# main_board.net
KiCad netlist of a schematic drawn in EAGLE
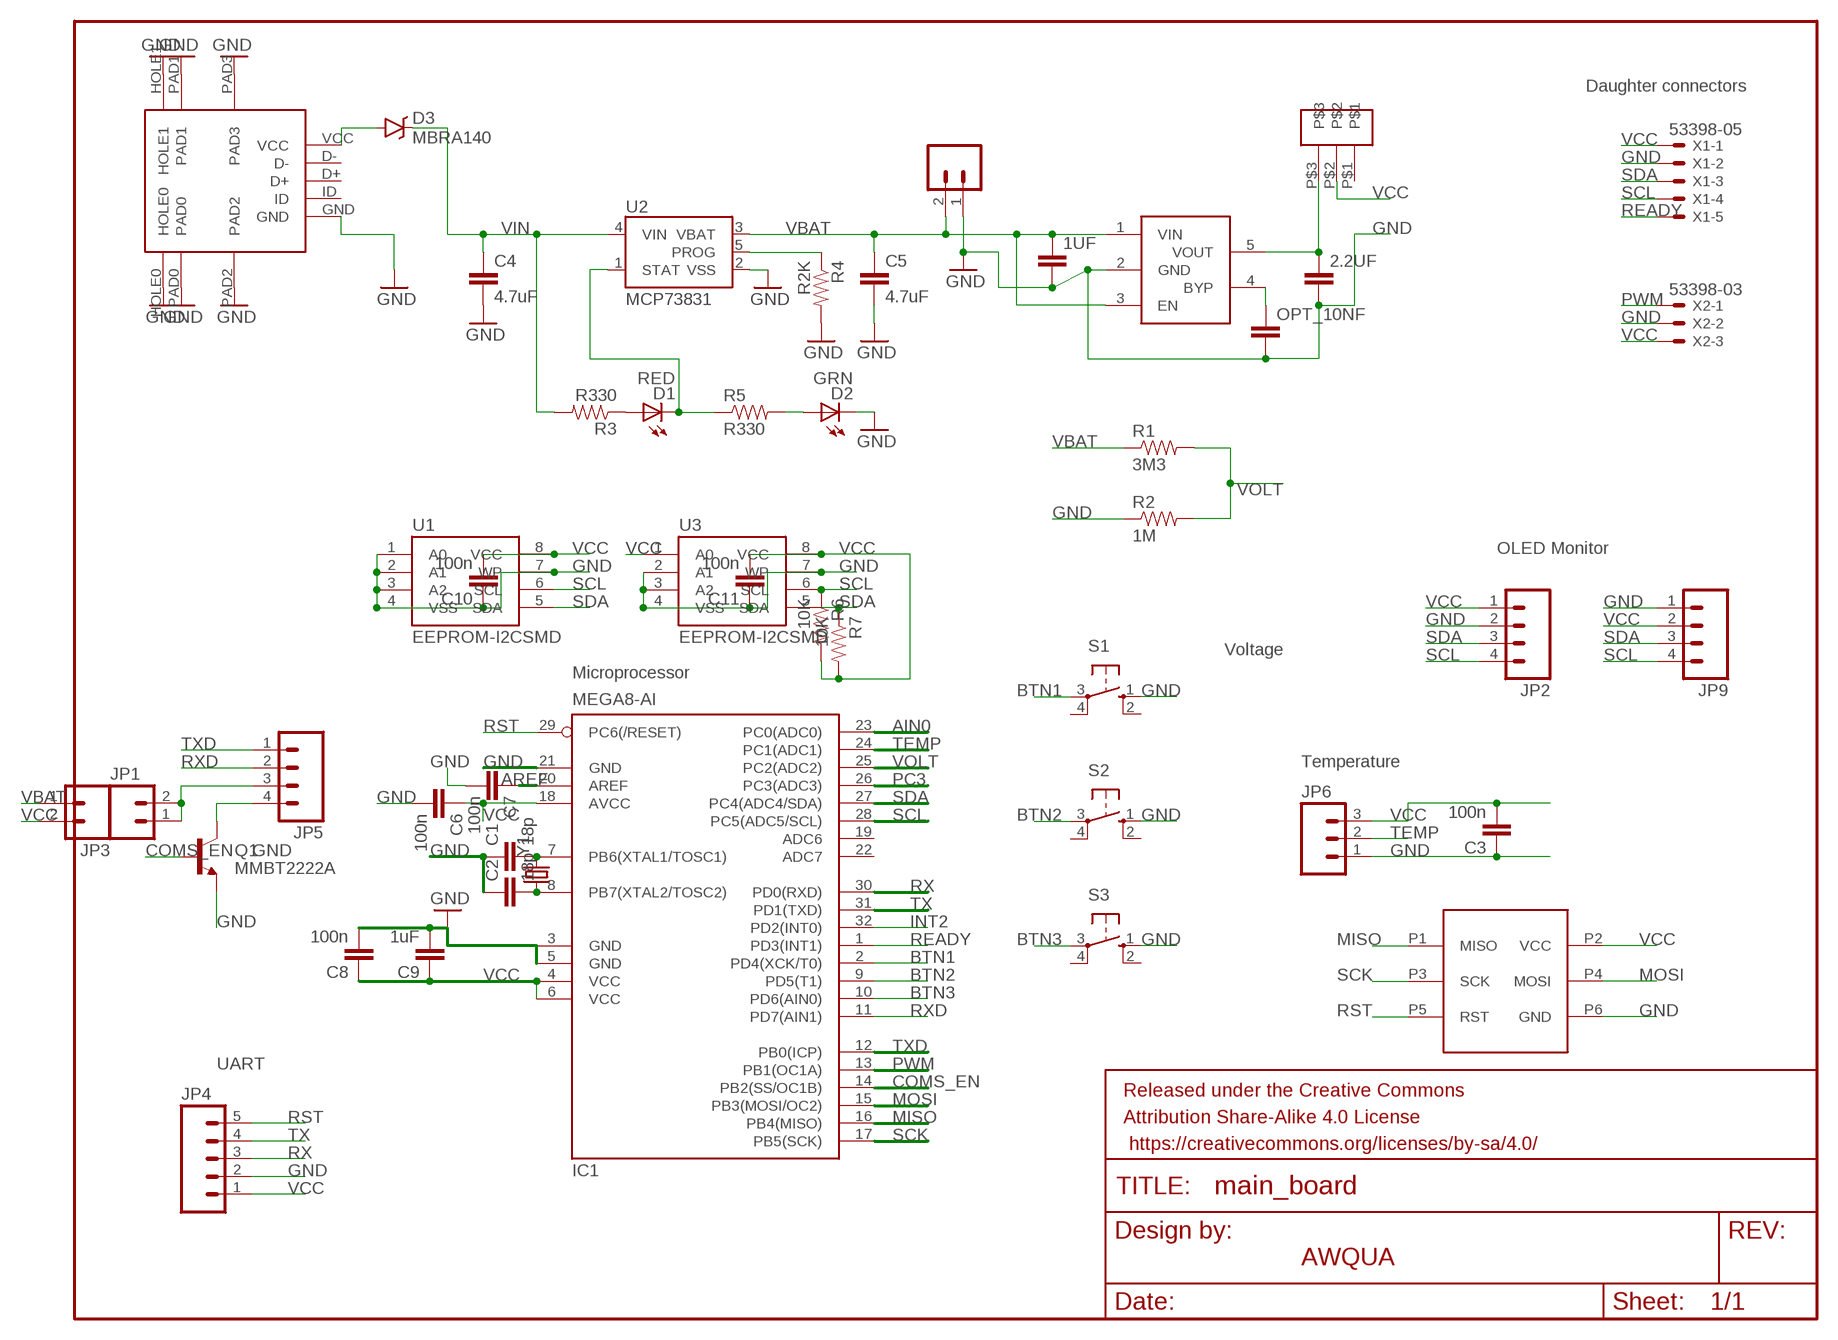
[diagram p0: schematic, sheet 1]

(export (version "E")
  (design (tool "Eeschema 10.0.6"))
  (components
    (comp (ref "1UF")
      (value "CAP0603-CAP")
      (footprint "eagle-import:0603-CAP")
      (libsource (lib "eagle-import") (part "SparkFun-Passives_CAP0603-CAP"))
    )
    (comp (ref "2.2UF")
      (value "CAP0603-CAP")
      (footprint "eagle-import:0603-CAP")
      (libsource (lib "eagle-import") (part "SparkFun-Passives_CAP0603-CAP"))
    )
    (comp (ref "C1")
      (value "18p")
      (footprint "eagle-import:0603-CAP")
      (libsource (lib "eagle-import") (part "CAP0603-CAP"))
    )
    (comp (ref "C2")
      (value "18p")
      (footprint "eagle-import:0603-CAP")
      (libsource (lib "eagle-import") (part "CAP0603-CAP"))
    )
    (comp (ref "C3")
      (value "100n")
      (footprint "eagle-import:0603-CAP")
      (libsource (lib "eagle-import") (part "CAP0603-CAP"))
    )
    (comp (ref "C4")
      (value "4.7uF")
      (footprint "eagle-import:0402-CAP")
      (libsource (lib "eagle-import") (part "CAP0402-CAP"))
    )
    (comp (ref "C5")
      (value "4.7uF")
      (footprint "eagle-import:0402-CAP")
      (libsource (lib "eagle-import") (part "CAP0402-CAP"))
    )
    (comp (ref "C6")
      (value "100n")
      (footprint "eagle-import:0603-CAP")
      (libsource (lib "eagle-import") (part "CAP0603-CAP"))
    )
    (comp (ref "C7")
      (value "100n")
      (footprint "eagle-import:0603-CAP")
      (libsource (lib "eagle-import") (part "CAP0603-CAP"))
    )
    (comp (ref "C8")
      (value "100n")
      (footprint "eagle-import:0603-CAP")
      (libsource (lib "eagle-import") (part "CAP0603-CAP"))
    )
    (comp (ref "C9")
      (value "1uF")
      (footprint "eagle-import:0603-CAP")
      (libsource (lib "eagle-import") (part "CAP0603-CAP"))
    )
    (comp (ref "C10")
      (value "100n")
      (footprint "eagle-import:0603-CAP")
      (libsource (lib "eagle-import") (part "CAP0603-CAP"))
    )
    (comp (ref "C11")
      (value "100n")
      (footprint "eagle-import:0603-CAP")
      (libsource (lib "eagle-import") (part "CAP0603-CAP"))
    )
    (comp (ref "D1")
      (value "RED")
      (footprint "eagle-import:LED-0603")
      (libsource (lib "eagle-import") (part "LED0603"))
    )
    (comp (ref "D2")
      (value "GRN")
      (footprint "eagle-import:LED-0603")
      (libsource (lib "eagle-import") (part "LED0603"))
    )
    (comp (ref "D3")
      (value "MBRA140")
      (footprint "eagle-import:SMA-DIODE")
      (libsource (lib "eagle-import") (part "MBRA140"))
    )
    (comp (ref "FRAME1")
      (value "FRAME-LETTER")
      (footprint "eagle-import:CREATIVE_COMMONS")
      (libsource (lib "eagle-import") (part "FRAME-LETTER"))
    )
    (comp (ref "IC1")
      (value "MEGA8-AI")
      (footprint "eagle-import:TQFP32-08")
      (fields (field (name "MPN") "ATMEGA8-16AU"))
      (libsource (lib "eagle-import") (part "MEGA8-AI"))
    )
    (comp (ref "JP1")
      (value "M02PTH")
      (footprint "eagle-import:1X02")
      (libsource (lib "eagle-import") (part "SparkFun-Connectors_M02PTH"))
    )
    (comp (ref "JP2")
      (value "M04PTH")
      (footprint "eagle-import:1X04")
      (libsource (lib "eagle-import") (part "M04PTH"))
    )
    (comp (ref "JP3")
      (value "M02PTH")
      (footprint "eagle-import:1X02")
      (libsource (lib "eagle-import") (part "SparkFun-Connectors_M02PTH"))
    )
    (comp (ref "JP4")
      (value "M05PTH")
      (footprint "eagle-import:1X05")
      (libsource (lib "eagle-import") (part "M05PTH"))
    )
    (comp (ref "JP5")
      (value "M04PTH")
      (footprint "eagle-import:1X04")
      (libsource (lib "eagle-import") (part "M04PTH"))
    )
    (comp (ref "JP6")
      (value "M03PTH")
      (footprint "eagle-import:1X03")
      (libsource (lib "eagle-import") (part "M03PTH"))
    )
    (comp (ref "JP7")
      (value "LiPo Battery")
      (footprint "eagle-import:JST-2-SMD")
      (libsource (lib "eagle-import") (part "M02-JST-2MM-SMT"))
    )
    (comp (ref "JP9")
      (value "M04PTH")
      (footprint "eagle-import:1X04")
      (libsource (lib "eagle-import") (part "M04PTH"))
    )
    (comp (ref "OPT_10NF")
      (value "CAP0603-CAP")
      (footprint "eagle-import:0603-CAP")
      (libsource (lib "eagle-import") (part "SparkFun-Passives_CAP0603-CAP"))
    )
    (comp (ref "Q1")
      (value "MMBT2222A")
      (footprint "eagle-import:SOT23-3")
      (libsource (lib "eagle-import") (part "TRANSISTOR_NPNMMBT2222A"))
    )
    (comp (ref "R1")
      (value "3M3")
      (footprint "eagle-import:0603-RES")
      (libsource (lib "eagle-import") (part "RESISTOR0603"))
    )
    (comp (ref "R2")
      (value "1M")
      (footprint "eagle-import:0603-RES")
      (libsource (lib "eagle-import") (part "RESISTOR0603"))
    )
    (comp (ref "R3")
      (value "R330")
      (footprint "eagle-import:0402-RES")
      (libsource (lib "eagle-import") (part "RESISTOR0402-RES"))
    )
    (comp (ref "R4")
      (value "R2K")
      (footprint "eagle-import:0402-RES")
      (libsource (lib "eagle-import") (part "RESISTOR0402-RES"))
    )
    (comp (ref "R5")
      (value "R330")
      (footprint "eagle-import:0402-RES")
      (libsource (lib "eagle-import") (part "RESISTOR0402-RES"))
    )
    (comp (ref "R6")
      (value "10K")
      (footprint "eagle-import:0402-RES")
      (libsource (lib "eagle-import") (part "RESISTOR0402-RES"))
    )
    (comp (ref "R7")
      (value "10K")
      (footprint "eagle-import:0402-RES")
      (libsource (lib "eagle-import") (part "RESISTOR0402-RES"))
    )
    (comp (ref "S1")
      (value "40-XX")
      (footprint "eagle-import:B3F-40XX")
      (fields (field (name "MF") "OMRON COMPONENTS USA") (field (name "MPN") "B3F-4000"))
      (libsource (lib "eagle-import") (part "40-XX"))
    )
    (comp (ref "S2")
      (value "40-XX")
      (footprint "eagle-import:B3F-40XX")
      (fields (field (name "MF") "OMRON COMPONENTS USA") (field (name "MPN") "B3F-4000"))
      (libsource (lib "eagle-import") (part "40-XX"))
    )
    (comp (ref "S3")
      (value "40-XX")
      (footprint "eagle-import:B3F-40XX")
      (fields (field (name "MF") "OMRON COMPONENTS USA") (field (name "MPN") "B3F-4000"))
      (libsource (lib "eagle-import") (part "40-XX"))
    )
    (comp (ref "U$1")
      (value "ISP-SMD-6PIN")
      (footprint "eagle-import:ISP-SMD-6PIN")
      (libsource (lib "eagle-import") (part "ISP-SMD-6PIN"))
    )
    (comp (ref "U$2")
      (value "OS102-SPDT-SWITCH")
      (footprint "eagle-import:OS102-SPDT-SWITCH")
      (libsource (lib "eagle-import") (part "OS102-SPDT-SWITCH"))
    )
    (comp (ref "U$3")
      (value "USBMICRO-10118193-0001LF")
      (footprint "eagle-import:USBMICRO-10118193-0001LF")
      (libsource (lib "eagle-import") (part "USBMICRO-10118193-0001LF"))
    )
    (comp (ref "U$6")
      (value "LP2985")
      (footprint "eagle-import:LP2985")
      (libsource (lib "eagle-import") (part "LP2985"))
    )
    (comp (ref "U1")
      (value "EEPROM-I2CSMD")
      (footprint "eagle-import:SO08")
      (libsource (lib "eagle-import") (part "EEPROM-I2CSMD"))
    )
    (comp (ref "U2")
      (value "MCP73831")
      (footprint "eagle-import:SOT23-5")
      (libsource (lib "eagle-import") (part "MCP73831"))
    )
    (comp (ref "U3")
      (value "EEPROM-I2CSMD")
      (footprint "eagle-import:SO08")
      (libsource (lib "eagle-import") (part "EEPROM-I2CSMD"))
    )
    (comp (ref "X1")
      (value "53398-05")
      (footprint "eagle-import:53398-05")
      (libsource (lib "eagle-import") (part "53?-05398"))
    )
    (comp (ref "X2")
      (value "53398-03")
      (footprint "eagle-import:53398-03")
      (libsource (lib "eagle-import") (part "53?-03398"))
    )
    (comp (ref "Y1")
      (value "CRYSTAL5X3")
      (footprint "eagle-import:CRYSTAL-SMD-5X3")
      (libsource (lib "eagle-import") (part "CRYSTAL5X3"))
    )
  )
  (nets
    (net (code "1") (name "/AIN0") (class "Default")
      (node (ref "IC1") (pin "23") (pinfunction "PC0(ADC0)_23") (pintype "bidirectional"))
    )
    (net (code "2") (name "/AREF") (class "Default")
      (node (ref "C7") (pin "1") (pinfunction "1_1") (pintype "passive"))
      (node (ref "IC1") (pin "20") (pinfunction "AREF_20") (pintype "passive"))
    )
    (net (code "3") (name "/BTN1") (class "Default")
      (node (ref "IC1") (pin "2") (pinfunction "PD4(XCK/T0)_2") (pintype "bidirectional"))
      (node (ref "S1") (pin "3") (pinfunction "P_3") (pintype "passive"))
    )
    (net (code "4") (name "/BTN2") (class "Default")
      (node (ref "IC1") (pin "9") (pinfunction "PD5(T1)_9") (pintype "bidirectional"))
      (node (ref "S2") (pin "3") (pinfunction "P_3") (pintype "passive"))
    )
    (net (code "5") (name "/BTN3") (class "Default")
      (node (ref "IC1") (pin "10") (pinfunction "PD6(AIN0)_10") (pintype "bidirectional"))
      (node (ref "S3") (pin "3") (pinfunction "P_3") (pintype "passive"))
    )
    (net (code "6") (name "/COMS_EN") (class "Default")
      (node (ref "IC1") (pin "14") (pinfunction "PB2(SS/OC1B)_14") (pintype "bidirectional"))
      (node (ref "Q1") (pin "1") (pinfunction "B_1") (pintype "passive"))
    )
    (net (code "7") (name "/INT2") (class "Default")
      (node (ref "IC1") (pin "32") (pinfunction "PD2(INT0)_32") (pintype "bidirectional"))
    )
    (net (code "8") (name "/MISO") (class "Default")
      (node (ref "IC1") (pin "16") (pinfunction "PB4(MISO)_16") (pintype "bidirectional"))
      (node (ref "U$1") (pin "P1") (pinfunction "MISO_P1") (pintype "bidirectional"))
    )
    (net (code "9") (name "/MOSI") (class "Default")
      (node (ref "IC1") (pin "15") (pinfunction "PB3(MOSI/OC2)_15") (pintype "bidirectional"))
      (node (ref "U$1") (pin "P4") (pinfunction "MOSI_P4") (pintype "bidirectional"))
    )
    (net (code "10") (name "/PC3") (class "Default")
      (node (ref "IC1") (pin "26") (pinfunction "PC3(ADC3)_26") (pintype "bidirectional"))
    )
    (net (code "11") (name "/PWM") (class "Default")
      (node (ref "IC1") (pin "13") (pinfunction "PB1(OC1A)_13") (pintype "bidirectional"))
      (node (ref "X2") (pin "1") (pinfunction "S_1") (pintype "passive"))
    )
    (net (code "12") (name "/READY") (class "Default")
      (node (ref "IC1") (pin "1") (pinfunction "PD3(INT1)_1") (pintype "bidirectional"))
      (node (ref "X1") (pin "5") (pinfunction "S_5") (pintype "passive"))
    )
    (net (code "13") (name "/RST") (class "Default")
      (node (ref "IC1") (pin "29") (pinfunction "PC6(/RESET)_29") (pintype "bidirectional"))
      (node (ref "JP4") (pin "5") (pinfunction "5_5") (pintype "passive"))
      (node (ref "U$1") (pin "P5") (pinfunction "RST_P5") (pintype "bidirectional"))
    )
    (net (code "14") (name "/RX") (class "Default")
      (node (ref "IC1") (pin "30") (pinfunction "PD0(RXD)_30") (pintype "bidirectional"))
      (node (ref "JP4") (pin "3") (pinfunction "3_3") (pintype "passive"))
    )
    (net (code "15") (name "/RXD") (class "Default")
      (node (ref "IC1") (pin "11") (pinfunction "PD7(AIN1)_11") (pintype "bidirectional"))
      (node (ref "JP5") (pin "2") (pinfunction "2_2") (pintype "passive"))
    )
    (net (code "16") (name "/SCK") (class "Default")
      (node (ref "IC1") (pin "17") (pinfunction "PB5(SCK)_17") (pintype "bidirectional"))
      (node (ref "U$1") (pin "P3") (pinfunction "SCK_P3") (pintype "bidirectional"))
    )
    (net (code "17") (name "/SCL") (class "Default")
      (node (ref "IC1") (pin "28") (pinfunction "PC5(ADC5/SCL)_28") (pintype "bidirectional"))
      (node (ref "JP2") (pin "4") (pinfunction "4_4") (pintype "passive"))
      (node (ref "JP9") (pin "4") (pinfunction "4_4") (pintype "passive"))
      (node (ref "R6") (pin "1") (pinfunction "1_1") (pintype "passive"))
      (node (ref "U1") (pin "6") (pinfunction "SCL_6") (pintype "bidirectional"))
      (node (ref "U3") (pin "6") (pinfunction "SCL_6") (pintype "bidirectional"))
      (node (ref "X1") (pin "4") (pinfunction "S_4") (pintype "passive"))
    )
    (net (code "18") (name "/SDA") (class "Default")
      (node (ref "IC1") (pin "27") (pinfunction "PC4(ADC4/SDA)_27") (pintype "bidirectional"))
      (node (ref "JP2") (pin "3") (pinfunction "3_3") (pintype "passive"))
      (node (ref "JP9") (pin "3") (pinfunction "3_3") (pintype "passive"))
      (node (ref "R7") (pin "1") (pinfunction "1_1") (pintype "passive"))
      (node (ref "U1") (pin "5") (pinfunction "SDA_5") (pintype "bidirectional"))
      (node (ref "U3") (pin "5") (pinfunction "SDA_5") (pintype "bidirectional"))
      (node (ref "X1") (pin "3") (pinfunction "S_3") (pintype "passive"))
    )
    (net (code "19") (name "/TEMP") (class "Default")
      (node (ref "IC1") (pin "24") (pinfunction "PC1(ADC1)_24") (pintype "bidirectional"))
      (node (ref "JP6") (pin "2") (pinfunction "2_2") (pintype "passive"))
    )
    (net (code "20") (name "/TX") (class "Default")
      (node (ref "IC1") (pin "31") (pinfunction "PD1(TXD)_31") (pintype "bidirectional"))
      (node (ref "JP4") (pin "4") (pinfunction "4_4") (pintype "passive"))
    )
    (net (code "21") (name "/TXD") (class "Default")
      (node (ref "IC1") (pin "12") (pinfunction "PB0(ICP)_12") (pintype "bidirectional"))
      (node (ref "JP5") (pin "1") (pinfunction "1_1") (pintype "passive"))
    )
    (net (code "22") (name "/VBAT") (class "Default")
      (node (ref "1UF") (pin "1") (pinfunction "1_1") (pintype "passive"))
      (node (ref "C5") (pin "1") (pinfunction "1_1") (pintype "passive"))
      (node (ref "JP3") (pin "1") (pinfunction "1_1") (pintype "passive"))
      (node (ref "JP7") (pin "2") (pinfunction "2_2") (pintype "passive"))
      (node (ref "R1") (pin "1") (pinfunction "1_1") (pintype "passive"))
      (node (ref "U$6") (pin "1") (pinfunction "VIN_1") (pintype "bidirectional"))
      (node (ref "U$6") (pin "3") (pinfunction "EN_3") (pintype "bidirectional"))
      (node (ref "U2") (pin "3") (pinfunction "VBAT_3") (pintype "power_in"))
    )
    (net (code "23") (name "/VCC") (class "Default")
      (node (ref "C10") (pin "2") (pinfunction "2_2") (pintype "passive"))
      (node (ref "C11") (pin "2") (pinfunction "2_2") (pintype "passive"))
      (node (ref "C3") (pin "2") (pinfunction "2_2") (pintype "passive"))
      (node (ref "C6") (pin "1") (pinfunction "1_1") (pintype "passive"))
      (node (ref "C8") (pin "1") (pinfunction "1_1") (pintype "passive"))
      (node (ref "C9") (pin "1") (pinfunction "1_1") (pintype "passive"))
      (node (ref "IC1") (pin "18") (pinfunction "AVCC_18") (pintype "power_in"))
      (node (ref "IC1") (pin "4") (pinfunction "VCC_4") (pintype "power_in"))
      (node (ref "IC1") (pin "6") (pinfunction "VCC_6") (pintype "power_in"))
      (node (ref "JP2") (pin "1") (pinfunction "1_1") (pintype "passive"))
      (node (ref "JP3") (pin "2") (pinfunction "2_2") (pintype "passive"))
      (node (ref "JP4") (pin "1") (pinfunction "1_1") (pintype "passive"))
      (node (ref "JP6") (pin "3") (pinfunction "3_3") (pintype "passive"))
      (node (ref "JP9") (pin "2") (pinfunction "2_2") (pintype "passive"))
      (node (ref "R6") (pin "2") (pinfunction "2_2") (pintype "passive"))
      (node (ref "R7") (pin "2") (pinfunction "2_2") (pintype "passive"))
      (node (ref "U$1") (pin "P2") (pinfunction "VCC_P2") (pintype "bidirectional"))
      (node (ref "U$2") (pin "P$2") (pinfunction "P$2_P$2") (pintype "bidirectional"))
      (node (ref "U1") (pin "8") (pinfunction "VCC_8") (pintype "power_in"))
      (node (ref "U3") (pin "1") (pinfunction "A0_1") (pintype "bidirectional"))
      (node (ref "U3") (pin "8") (pinfunction "VCC_8") (pintype "power_in"))
      (node (ref "X1") (pin "1") (pinfunction "S_1") (pintype "passive"))
      (node (ref "X2") (pin "3") (pinfunction "S_3") (pintype "passive"))
    )
    (net (code "24") (name "/VIN") (class "Default")
      (node (ref "C4") (pin "1") (pinfunction "1_1") (pintype "passive"))
      (node (ref "D3") (pin "C") (pinfunction "C_C") (pintype "passive"))
      (node (ref "R3") (pin "2") (pinfunction "2_2") (pintype "passive"))
      (node (ref "U2") (pin "4") (pinfunction "VIN_4") (pintype "power_in"))
    )
    (net (code "25") (name "/VOLT") (class "Default")
      (node (ref "IC1") (pin "25") (pinfunction "PC2(ADC2)_25") (pintype "bidirectional"))
      (node (ref "R1") (pin "2") (pinfunction "2_2") (pintype "passive"))
      (node (ref "R2") (pin "2") (pinfunction "2_2") (pintype "passive"))
    )
    (net (code "26") (name "GND") (class "Default")
      (node (ref "1UF") (pin "2") (pinfunction "2_2") (pintype "passive"))
      (node (ref "2.2UF") (pin "2") (pinfunction "2_2") (pintype "passive"))
      (node (ref "C1") (pin "1") (pinfunction "1_1") (pintype "passive"))
      (node (ref "C10") (pin "1") (pinfunction "1_1") (pintype "passive"))
      (node (ref "C11") (pin "1") (pinfunction "1_1") (pintype "passive"))
      (node (ref "C2") (pin "1") (pinfunction "1_1") (pintype "passive"))
      (node (ref "C3") (pin "1") (pinfunction "1_1") (pintype "passive"))
      (node (ref "C4") (pin "2") (pinfunction "2_2") (pintype "passive"))
      (node (ref "C5") (pin "2") (pinfunction "2_2") (pintype "passive"))
      (node (ref "C6") (pin "2") (pinfunction "2_2") (pintype "passive"))
      (node (ref "C7") (pin "2") (pinfunction "2_2") (pintype "passive"))
      (node (ref "C8") (pin "2") (pinfunction "2_2") (pintype "passive"))
      (node (ref "C9") (pin "2") (pinfunction "2_2") (pintype "passive"))
      (node (ref "D2") (pin "C") (pinfunction "C_C") (pintype "passive"))
      (node (ref "IC1") (pin "21") (pinfunction "GND_21") (pintype "power_in"))
      (node (ref "IC1") (pin "3") (pinfunction "GND_3") (pintype "power_in"))
      (node (ref "IC1") (pin "5") (pinfunction "GND_5") (pintype "power_in"))
      (node (ref "JP2") (pin "2") (pinfunction "2_2") (pintype "passive"))
      (node (ref "JP4") (pin "2") (pinfunction "2_2") (pintype "passive"))
      (node (ref "JP5") (pin "4") (pinfunction "4_4") (pintype "passive"))
      (node (ref "JP6") (pin "1") (pinfunction "1_1") (pintype "passive"))
      (node (ref "JP7") (pin "1") (pinfunction "1_1") (pintype "passive"))
      (node (ref "JP9") (pin "1") (pinfunction "1_1") (pintype "passive"))
      (node (ref "OPT_10NF") (pin "2") (pinfunction "2_2") (pintype "passive"))
      (node (ref "Q1") (pin "2") (pinfunction "E_2") (pintype "passive"))
      (node (ref "Q1") (pin "3") (pinfunction "C_3") (pintype "passive"))
      (node (ref "R2") (pin "1") (pinfunction "1_1") (pintype "passive"))
      (node (ref "R4") (pin "2") (pinfunction "2_2") (pintype "passive"))
      (node (ref "S1") (pin "1") (pinfunction "S_1") (pintype "passive"))
      (node (ref "S2") (pin "1") (pinfunction "S_1") (pintype "passive"))
      (node (ref "S3") (pin "1") (pinfunction "S_1") (pintype "passive"))
      (node (ref "U$1") (pin "P6") (pinfunction "GND_P6") (pintype "bidirectional"))
      (node (ref "U$3") (pin "GND") (pinfunction "GND_GND") (pintype "bidirectional"))
      (node (ref "U$3") (pin "HOLE0") (pinfunction "HOLE0_HOLE0") (pintype "bidirectional"))
      (node (ref "U$3") (pin "HOLE1") (pinfunction "HOLE1_HOLE1") (pintype "bidirectional"))
      (node (ref "U$3") (pin "PAD0") (pinfunction "PAD0_PAD0") (pintype "bidirectional"))
      (node (ref "U$3") (pin "PAD1") (pinfunction "PAD1_PAD1") (pintype "bidirectional"))
      (node (ref "U$3") (pin "PAD2") (pinfunction "PAD2_PAD2") (pintype "bidirectional"))
      (node (ref "U$3") (pin "PAD3") (pinfunction "PAD3_PAD3") (pintype "bidirectional"))
      (node (ref "U$6") (pin "2") (pinfunction "GND_2") (pintype "bidirectional"))
      (node (ref "U1") (pin "1") (pinfunction "A0_1") (pintype "bidirectional"))
      (node (ref "U1") (pin "2") (pinfunction "A1_2") (pintype "bidirectional"))
      (node (ref "U1") (pin "3") (pinfunction "A2_3") (pintype "bidirectional"))
      (node (ref "U1") (pin "4") (pinfunction "VSS_4") (pintype "power_in"))
      (node (ref "U1") (pin "7") (pinfunction "WP_7") (pintype "bidirectional"))
      (node (ref "U2") (pin "2") (pinfunction "VSS_2") (pintype "power_in"))
      (node (ref "U3") (pin "2") (pinfunction "A1_2") (pintype "bidirectional"))
      (node (ref "U3") (pin "3") (pinfunction "A2_3") (pintype "bidirectional"))
      (node (ref "U3") (pin "4") (pinfunction "VSS_4") (pintype "power_in"))
      (node (ref "U3") (pin "7") (pinfunction "WP_7") (pintype "bidirectional"))
      (node (ref "X1") (pin "2") (pinfunction "S_2") (pintype "passive"))
      (node (ref "X2") (pin "2") (pinfunction "S_2") (pintype "passive"))
    )
    (net (code "27") (name "Net-(D1-PadA)") (class "Default")
      (node (ref "D1") (pin "A") (pinfunction "A_A") (pintype "passive"))
      (node (ref "R3") (pin "1") (pinfunction "1_1") (pintype "passive"))
    )
    (net (code "28") (name "Net-(D2-PadA)") (class "Default")
      (node (ref "D2") (pin "A") (pinfunction "A_A") (pintype "passive"))
      (node (ref "R5") (pin "2") (pinfunction "2_2") (pintype "passive"))
    )
    (net (code "29") (name "Net-(D3-PadA)") (class "Default")
      (node (ref "D3") (pin "A") (pinfunction "A_A") (pintype "passive"))
      (node (ref "U$3") (pin "VCC") (pinfunction "VCC_VCC") (pintype "bidirectional"))
    )
    (net (code "30") (name "Net-(IC1-PB6(XTAL1{slash}TOSC1))") (class "Default")
      (node (ref "C1") (pin "2") (pinfunction "2_2") (pintype "passive"))
      (node (ref "IC1") (pin "7") (pinfunction "PB6(XTAL1/TOSC1)_7") (pintype "bidirectional"))
      (node (ref "Y1") (pin "3") (pinfunction "2_3") (pintype "passive"))
    )
    (net (code "31") (name "Net-(IC1-PB7(XTAL2{slash}TOSC2))") (class "Default")
      (node (ref "C2") (pin "2") (pinfunction "2_2") (pintype "passive"))
      (node (ref "IC1") (pin "8") (pinfunction "PB7(XTAL2/TOSC2)_8") (pintype "bidirectional"))
      (node (ref "Y1") (pin "1") (pinfunction "1_1") (pintype "passive"))
    )
    (net (code "32") (name "Net-(JP1-Pad1)") (class "Default")
      (node (ref "JP1") (pin "1") (pinfunction "1_1") (pintype "passive"))
      (node (ref "JP1") (pin "2") (pinfunction "2_2") (pintype "passive"))
      (node (ref "JP5") (pin "3") (pinfunction "3_3") (pintype "passive"))
    )
    (net (code "33") (name "Net-(U$6-BYP)") (class "Default")
      (node (ref "OPT_10NF") (pin "1") (pinfunction "1_1") (pintype "passive"))
      (node (ref "U$6") (pin "4") (pinfunction "BYP_4") (pintype "bidirectional"))
    )
    (net (code "34") (name "Net-(U$6-VOUT)") (class "Default")
      (node (ref "2.2UF") (pin "1") (pinfunction "1_1") (pintype "passive"))
      (node (ref "U$2") (pin "P$3") (pinfunction "P$3_P$3") (pintype "bidirectional"))
      (node (ref "U$6") (pin "5") (pinfunction "VOUT_5") (pintype "bidirectional"))
    )
    (net (code "35") (name "Net-(U2-PROG)") (class "Default")
      (node (ref "R4") (pin "1") (pinfunction "1_1") (pintype "passive"))
      (node (ref "U2") (pin "5") (pinfunction "PROG_5") (pintype "input"))
    )
    (net (code "36") (name "Net-(U2-STAT)") (class "Default")
      (node (ref "D1") (pin "C") (pinfunction "C_C") (pintype "passive"))
      (node (ref "R5") (pin "1") (pinfunction "1_1") (pintype "passive"))
      (node (ref "U2") (pin "1") (pinfunction "STAT_1") (pintype "output"))
    )
    (net (code "37") (name "unconnected-(IC1-ADC6-Pad19)") (class "Default")
      (node (ref "IC1") (pin "19") (pinfunction "ADC6_19") (pintype "bidirectional"))
    )
    (net (code "38") (name "unconnected-(IC1-ADC7-Pad22)") (class "Default")
      (node (ref "IC1") (pin "22") (pinfunction "ADC7_22") (pintype "bidirectional"))
    )
    (net (code "39") (name "unconnected-(S1-P1-Pad4)") (class "Default")
      (node (ref "S1") (pin "4") (pinfunction "P1_4") (pintype "passive"))
    )
    (net (code "40") (name "unconnected-(S1-S1-Pad2)") (class "Default")
      (node (ref "S1") (pin "2") (pinfunction "S1_2") (pintype "passive"))
    )
    (net (code "41") (name "unconnected-(S2-P1-Pad4)") (class "Default")
      (node (ref "S2") (pin "4") (pinfunction "P1_4") (pintype "passive"))
    )
    (net (code "42") (name "unconnected-(S2-S1-Pad2)") (class "Default")
      (node (ref "S2") (pin "2") (pinfunction "S1_2") (pintype "passive"))
    )
    (net (code "43") (name "unconnected-(S3-P1-Pad4)") (class "Default")
      (node (ref "S3") (pin "4") (pinfunction "P1_4") (pintype "passive"))
    )
    (net (code "44") (name "unconnected-(S3-S1-Pad2)") (class "Default")
      (node (ref "S3") (pin "2") (pinfunction "S1_2") (pintype "passive"))
    )
    (net (code "45") (name "unconnected-(U$2-PadP$1)") (class "Default")
      (node (ref "U$2") (pin "P$1") (pinfunction "P$1_P$1") (pintype "bidirectional"))
    )
    (net (code "46") (name "unconnected-(U$3-PadD+)") (class "Default")
      (node (ref "U$3") (pin "D+") (pinfunction "D+_D+") (pintype "bidirectional"))
    )
    (net (code "47") (name "unconnected-(U$3-PadD-)") (class "Default")
      (node (ref "U$3") (pin "D-") (pinfunction "D-_D-") (pintype "bidirectional"))
    )
    (net (code "48") (name "unconnected-(U$3-PadID)") (class "Default")
      (node (ref "U$3") (pin "ID") (pinfunction "ID_ID") (pintype "bidirectional"))
    )
  )
)
